# POWER.net
KiCad netlist of a schematic drawn in Altium Designer
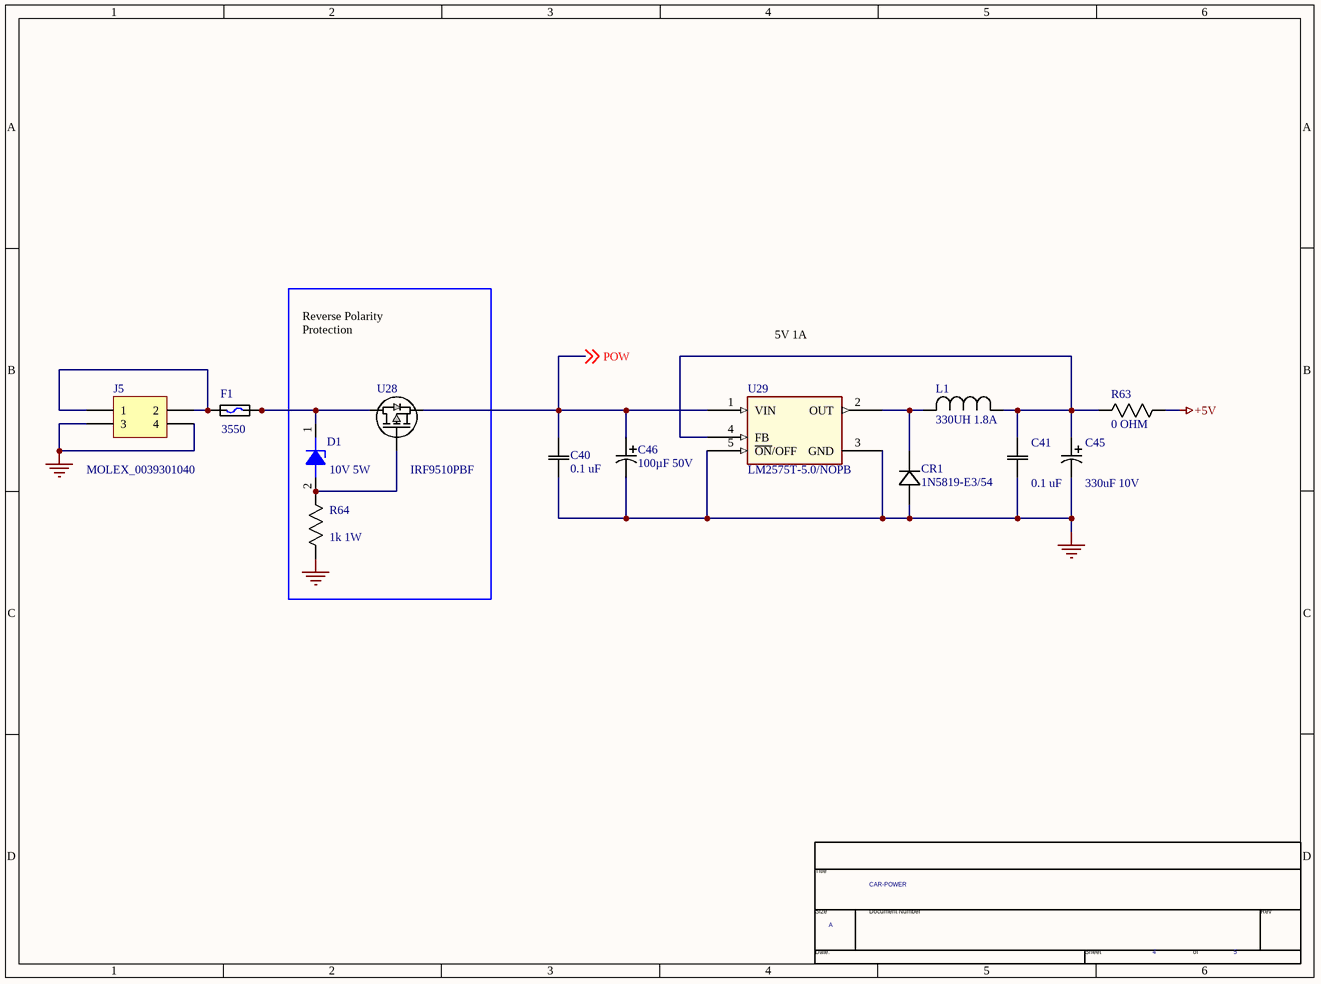
[diagram p0: POWER.SchDoc]

(export (version "E")
  (design (tool "Eeschema 10.0.6"))
  (components
    (comp (ref "C40")
      (value "0.1 uF")
      (footprint "SR20")
      (description "0.1µF ±10% 100V Ceramic Capacitor X7R Radial")
      (fields (field (name "MANUFACTURER_PART_NUMBER") "C320C104K1R5TA7301"))
      (libsource (lib "Discrete") (part "CAP RADIAL 2.54"))
    )
    (comp (ref "C41")
      (value "0.1 uF")
      (footprint "SR20")
      (description "0.1µF ±10% 100V Ceramic Capacitor X7R Radial")
      (fields (field (name "MANUFACTURER_PART_NUMBER") "C320C104K1R5TA7301"))
      (libsource (lib "Discrete") (part "CAP RADIAL 2.54"))
    )
    (comp (ref "C45")
      (value "330uF 10V")
      (footprint "PCAP_63x112")
      (description "CAP ALUM 330UF 20% 10V RADIAL")
      (fields (field (name "MANUFACTURER_PART_NUMBER") "ECA-1AM331"))
      (libsource (lib "Discrete") (part "PCAP_63x112"))
    )
    (comp (ref "C46")
      (value "100µF 50V")
      (footprint "PCAP_8x112")
      (description "CAP ALUM 100UF 20% 50V RADIAL")
      (fields (field (name "MANUFACTURER_PART_NUMBER") "ECA-1HM101"))
      (libsource (lib "Discrete") (part "PCAP_8x112"))
    )
    (comp (ref "CR1")
      (value "1N5819-E3/54")
      (footprint "Discrete:DO-204AL")
      (description "DIODE SCHOTTKY 40V 1A DO204AL")
      (libsource (lib "Discrete") (part "1N5819-E3/54"))
    )
    (comp (ref "D1")
      (value "10V 5W")
      (footprint "CASE_17AA-01")
      (description "DIODE ZENER 10V 5W AXIAL")
      (fields (field (name "MANUFACTURER_PART_NUMBER") "1N5347BRLG"))
      (libsource (lib "Discrete") (part "1N5347BRLG"))
    )
    (comp (ref "F1")
      (value "3550")
      (footprint "FUSE_CLIP_BLADE_HORIZONTAL")
      (description "FUSE CLIP BLADE 500V 30A PCB")
      (fields (field (name "MF") "Keystone Electronics"))
      (libsource (lib "Discrete") (part "FUSE_CLIP_BLADE_HORIZONTAL"))
    )
    (comp (ref "J5")
      (value "MOLEX_0039301040")
      (footprint "MOLEX_0039301040")
      (description "Header, 2-Pin, Dual row")
      (fields (field (name "PUBLISHER") "Altium Limited"))
      (libsource (lib "Miscellaneous Connectors") (part "Header 2X2"))
    )
    (comp (ref "L1")
      (value "330UH 1.8A")
      (footprint "AIUR-15")
      (description "FIXED IND 330UH 1.8A 260 MOHM TH")
      (fields (field (name "MANUFACTURER_PART_NUMBER") "AIUR-15-331K-ND"))
      (libsource (lib "Discrete") (part "AIUR-15-331K"))
    )
    (comp (ref "R63")
      (value "0 OHM")
      (footprint "RES AXIAL 1/6W")
      (description "RES 0 OHM 1/6W JUMP AXIAL")
      (fields (field (name "MANUFACTURER_PART_NUMBER") "ZOR-12-B-52-0R"))
      (libsource (lib "Discrete") (part "Resistor Axial  1/6W"))
    )
    (comp (ref "R64")
      (value "1k 1W")
      (footprint "YAG_FMP100")
      (description "RES 1K OHM 1W 5% AXIAL")
      (fields (field (name "MANUFACTURER_PART_NUMBER") "FMP100JR-52-1K"))
      (libsource (lib "Discrete") (part "Resistor Axial  1W"))
    )
    (comp (ref "U28")
      (value "IRF9510PBF")
      (footprint "TO220HS")
      (description "Imported")
      (libsource (lib "Discrete") (part "IRF9510PBF"))
    )
    (comp (ref "U29")
      (value "LM2575T-5.0/NOPB")
      (footprint "TO-220-5HS")
      (description "IC REG BUCK 5V 1A TO220-5")
      (libsource (lib "ICs") (part "LM2575T-5.0/NOPB"))
    )
  )
  (nets
    (net (code "1") (name "+5V") (class "Default")
      (node (ref "R63") (pin "1") (pinfunction "1_1") (pintype "passive"))
    )
    (net (code "2") (name "GND") (class "Default")
      (node (ref "C40") (pin "1") (pinfunction "1_1") (pintype "passive"))
      (node (ref "C41") (pin "1") (pinfunction "1_1") (pintype "passive"))
      (node (ref "C45") (pin "2") (pinfunction "2_2") (pintype "passive"))
      (node (ref "C46") (pin "2") (pinfunction "2_2") (pintype "passive"))
      (node (ref "CR1") (pin "2") (pinfunction "2_2") (pintype "passive"))
      (node (ref "J5") (pin "3") (pinfunction "3_3") (pintype "passive"))
      (node (ref "J5") (pin "4") (pinfunction "4_4") (pintype "passive"))
      (node (ref "R64") (pin "1") (pinfunction "1_1") (pintype "passive"))
      (node (ref "U29") (pin "3") (pinfunction "GND_3") (pintype "power_in"))
      (node (ref "U29") (pin "5") (pinfunction "~{ON}/OFF_5") (pintype "input"))
    )
    (net (code "3") (name "Net-(D1-ANODE)") (class "Default")
      (node (ref "D1") (pin "2") (pinfunction "ANODE_2") (pintype "passive"))
      (node (ref "R64") (pin "2") (pinfunction "2_2") (pintype "passive"))
      (node (ref "U28") (pin "1") (pinfunction "G_1") (pintype "passive"))
    )
    (net (code "4") (name "Net-(D1-CATHODE)") (class "Default")
      (node (ref "D1") (pin "1") (pinfunction "CATHODE_1") (pintype "passive"))
      (node (ref "F1") (pin "2A") (pinfunction "2_2A") (pintype "passive"))
      (node (ref "F1") (pin "2B") (pinfunction "2_2B") (pintype "passive"))
      (node (ref "U28") (pin "2") (pinfunction "D_2") (pintype "passive"))
    )
    (net (code "5") (name "Net-(F1-1-Pad1A)") (class "Default")
      (node (ref "F1") (pin "1A") (pinfunction "1_1A") (pintype "passive"))
      (node (ref "F1") (pin "1B") (pinfunction "1_1B") (pintype "passive"))
      (node (ref "J5") (pin "1") (pinfunction "1_1") (pintype "passive"))
      (node (ref "J5") (pin "2") (pinfunction "2_2") (pintype "passive"))
    )
    (net (code "6") (name "Net-(U29-FB)") (class "Default")
      (node (ref "C41") (pin "2") (pinfunction "2_2") (pintype "passive"))
      (node (ref "C45") (pin "1") (pinfunction "1_1") (pintype "passive"))
      (node (ref "L1") (pin "1") (pinfunction "1_1") (pintype "passive"))
      (node (ref "R63") (pin "2") (pinfunction "2_2") (pintype "passive"))
      (node (ref "U29") (pin "4") (pinfunction "FB_4") (pintype "input"))
    )
    (net (code "7") (name "Net-(U29-OUT)") (class "Default")
      (node (ref "CR1") (pin "1") (pinfunction "1_1") (pintype "passive"))
      (node (ref "L1") (pin "2") (pinfunction "2_2") (pintype "passive"))
      (node (ref "U29") (pin "2") (pinfunction "OUT_2") (pintype "output"))
    )
    (net (code "8") (name "POW") (class "Default")
      (node (ref "C40") (pin "2") (pinfunction "2_2") (pintype "passive"))
      (node (ref "C46") (pin "1") (pinfunction "1_1") (pintype "passive"))
      (node (ref "U28") (pin "3") (pinfunction "S_3") (pintype "passive"))
      (node (ref "U29") (pin "1") (pinfunction "VIN_1") (pintype "input"))
    )
  )
)
